# TPS2511.net
KiCad netlist of a schematic drawn in EAGLE
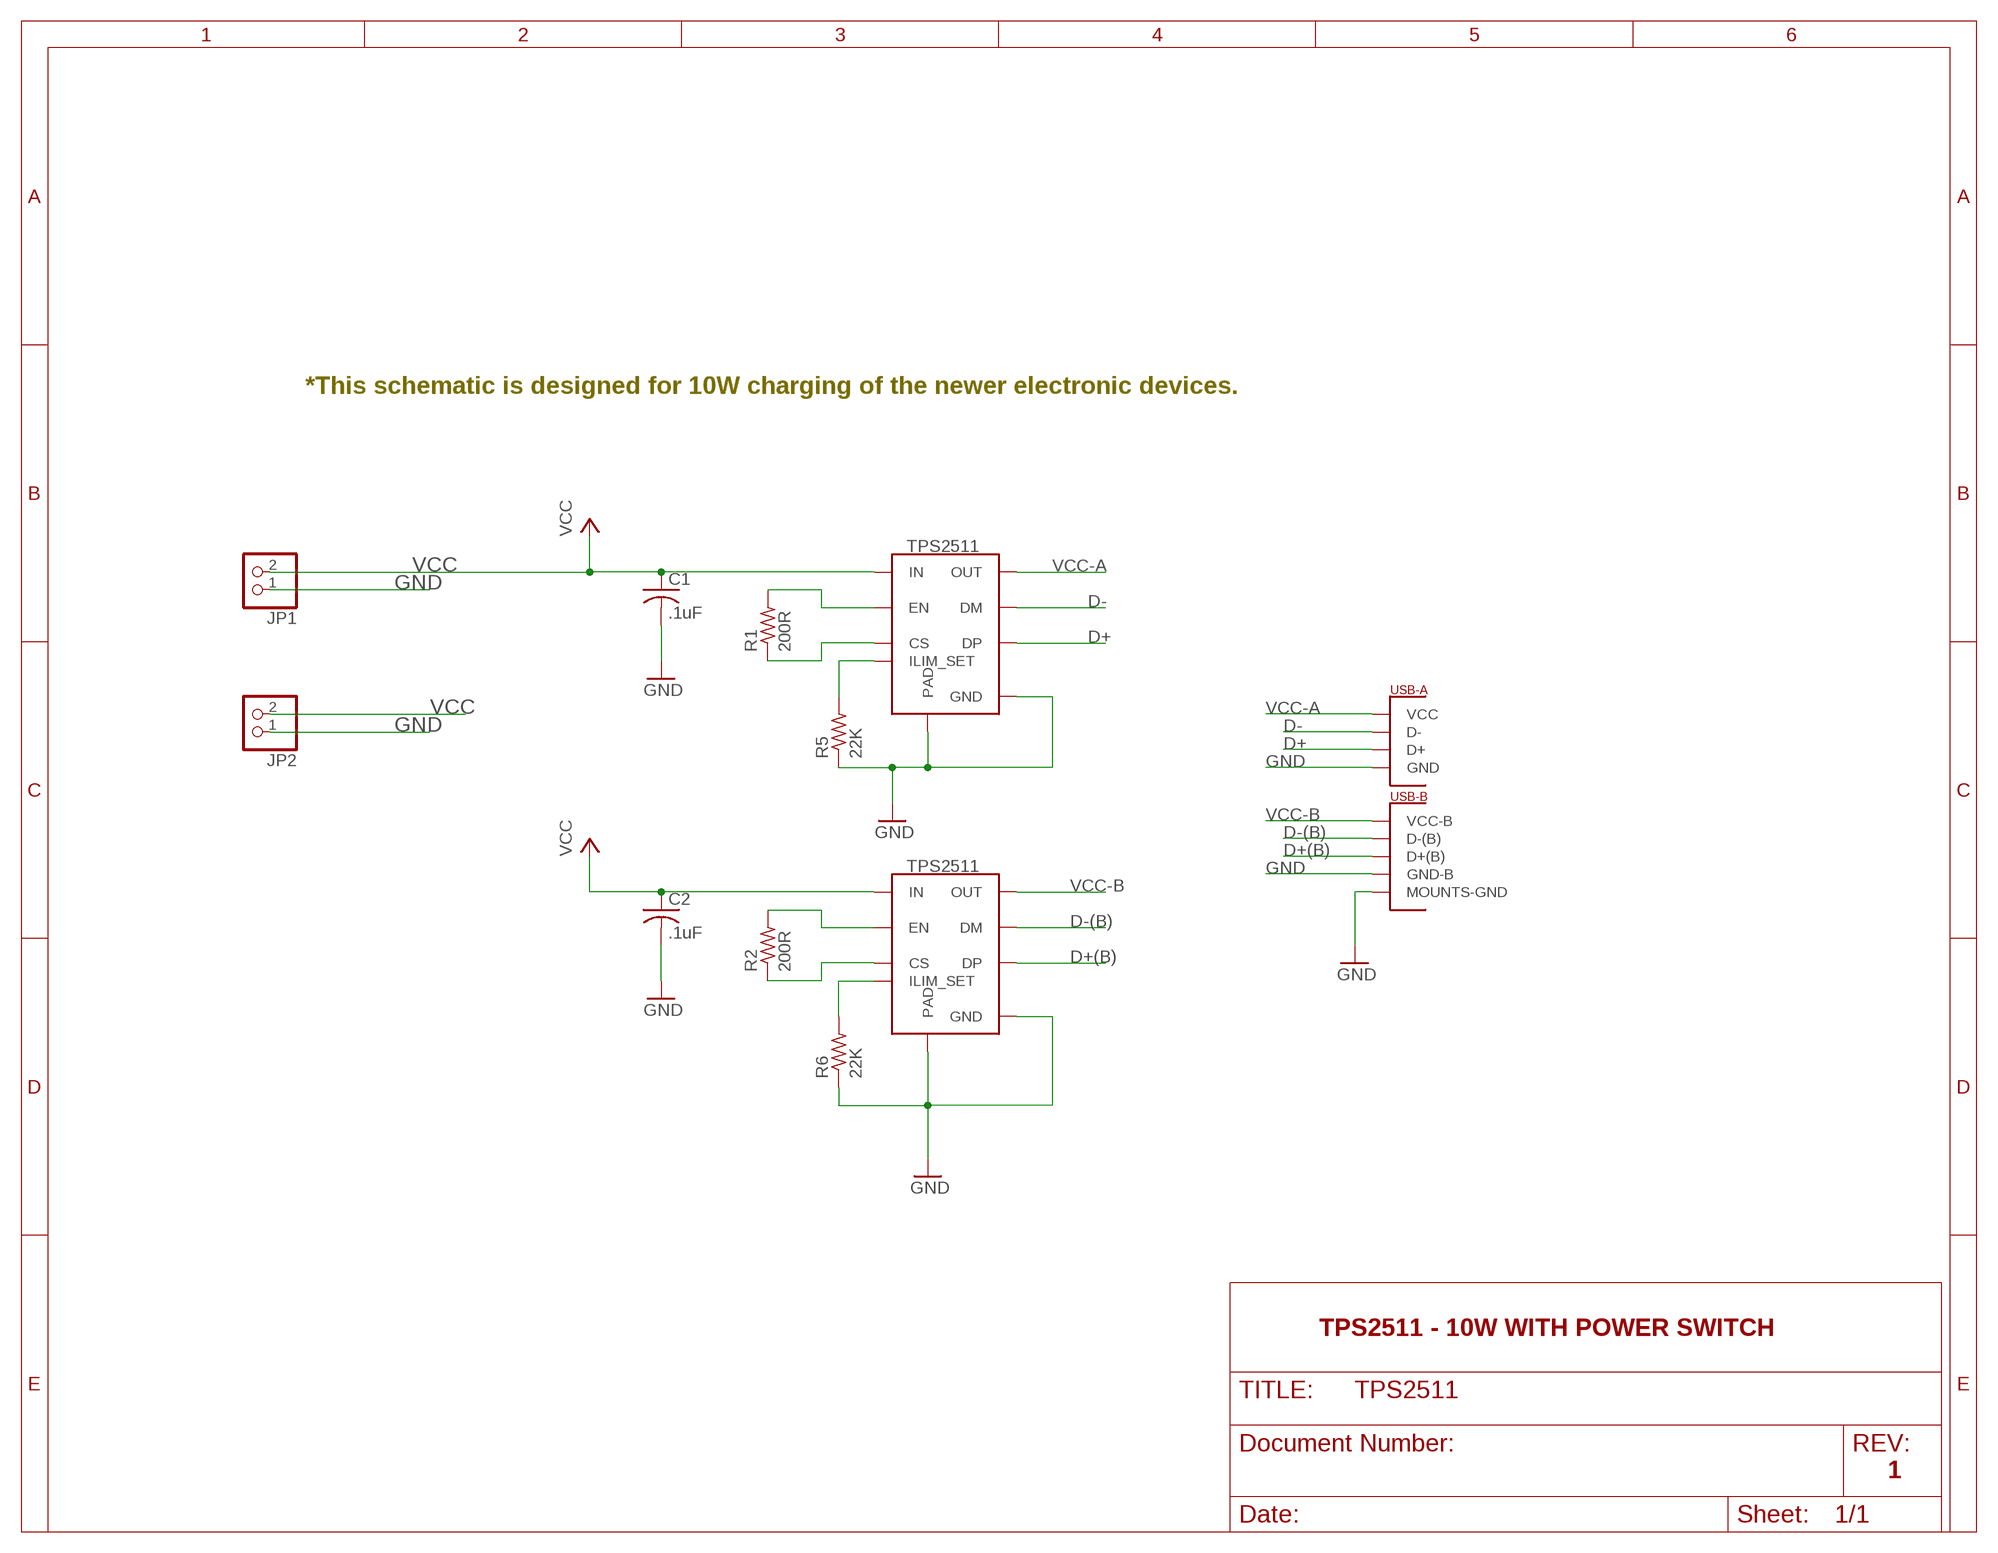
[diagram p0: schematic, sheet 1]

(export (version "E")
  (design (tool "Eeschema 10.0.6"))
  (components
    (comp (ref "C1")
      (value ".1uF")
      (footprint "eagle-import:C050-024X044")
      (libsource (lib "eagle-import") (part "C-US050-024X044"))
    )
    (comp (ref "C2")
      (value ".1uF")
      (footprint "eagle-import:C050-024X044")
      (libsource (lib "eagle-import") (part "C-US050-024X044"))
    )
    (comp (ref "JP1")
      (value "PINHD-1X2/90")
      (footprint "eagle-import:1X02_90")
      (libsource (lib "eagle-import") (part "PINHD-1X2/90"))
    )
    (comp (ref "JP2")
      (value "PINHD-1X2/90")
      (footprint "eagle-import:1X02_90")
      (libsource (lib "eagle-import") (part "PINHD-1X2/90"))
    )
    (comp (ref "R1")
      (value "200R")
      (footprint "eagle-import:0204_7")
      (libsource (lib "eagle-import") (part "R-US_0204/7"))
    )
    (comp (ref "R2")
      (value "200R")
      (footprint "eagle-import:0204_7")
      (libsource (lib "eagle-import") (part "R-US_0204/7"))
    )
    (comp (ref "R5")
      (value "22K")
      (footprint "eagle-import:0204_7")
      (libsource (lib "eagle-import") (part "R-US_0204/7"))
    )
    (comp (ref "R6")
      (value "22K")
      (footprint "eagle-import:0204_7")
      (libsource (lib "eagle-import") (part "R-US_0204/7"))
    )
    (comp (ref "U$1")
      (value "TPS2511-MSOP8")
      (footprint "eagle-import:MSOP-8")
      (libsource (lib "eagle-import") (part "TPS2511-MSOP8"))
    )
    (comp (ref "U$2")
      (value "DUAL-PORT-USB-REC")
      (footprint "eagle-import:DUAL-PORT-USB")
      (libsource (lib "eagle-import") (part "DUAL-PORT-USB-REC"))
    )
    (comp (ref "U$3")
      (value "TPS2511-MSOP8")
      (footprint "eagle-import:MSOP-8")
      (libsource (lib "eagle-import") (part "TPS2511-MSOP8"))
    )
  )
  (nets
    (net (code "1") (name "/D+") (class "Default")
      (node (ref "U$1") (pin "P$6") (pinfunction "DP_P$6") (pintype "bidirectional"))
      (node (ref "U$2") (pin "P$8") (pinfunction "D+_P$8") (pintype "bidirectional"))
    )
    (net (code "2") (name "/D+(B)") (class "Default")
      (node (ref "U$2") (pin "P$6") (pinfunction "D+(B)_P$6") (pintype "bidirectional"))
      (node (ref "U$3") (pin "P$6") (pinfunction "DP_P$6") (pintype "bidirectional"))
    )
    (net (code "3") (name "/D-") (class "Default")
      (node (ref "U$1") (pin "P$7") (pinfunction "DM_P$7") (pintype "bidirectional"))
      (node (ref "U$2") (pin "P$7") (pinfunction "D-_P$7") (pintype "bidirectional"))
    )
    (net (code "4") (name "/D-(B)") (class "Default")
      (node (ref "U$2") (pin "P$5") (pinfunction "D-(B)_P$5") (pintype "bidirectional"))
      (node (ref "U$3") (pin "P$7") (pinfunction "DM_P$7") (pintype "bidirectional"))
    )
    (net (code "5") (name "/VCC-A") (class "Default")
      (node (ref "U$1") (pin "P$8") (pinfunction "OUT_P$8") (pintype "power_in"))
      (node (ref "U$2") (pin "P$12") (pinfunction "VCC_P$12") (pintype "power_in"))
    )
    (net (code "6") (name "/VCC-B") (class "Default")
      (node (ref "U$2") (pin "P$10") (pinfunction "VCC-B_P$10") (pintype "power_in"))
      (node (ref "U$3") (pin "P$8") (pinfunction "OUT_P$8") (pintype "power_in"))
    )
    (net (code "7") (name "GND") (class "Default")
      (node (ref "C1") (pin "2") (pinfunction "2_2") (pintype "passive"))
      (node (ref "C2") (pin "2") (pinfunction "2_2") (pintype "passive"))
      (node (ref "JP1") (pin "1") (pinfunction "1_1") (pintype "passive"))
      (node (ref "JP2") (pin "1") (pinfunction "1_1") (pintype "passive"))
      (node (ref "R5") (pin "1") (pinfunction "1_1") (pintype "passive"))
      (node (ref "R6") (pin "1") (pinfunction "1_1") (pintype "passive"))
      (node (ref "U$1") (pin "P$1") (pinfunction "GND_P$1") (pintype "power_in"))
      (node (ref "U$1") (pin "P$9") (pinfunction "PAD_P$9") (pintype "power_in"))
      (node (ref "U$2") (pin "GND") (pinfunction "MOUNTS-GND_GND") (pintype "power_in"))
      (node (ref "U$2") (pin "P$11") (pinfunction "GND_P$11") (pintype "power_in"))
      (node (ref "U$2") (pin "P$2") (pinfunction "MOUNTS-GND_P$2") (pintype "power_in"))
      (node (ref "U$2") (pin "P$3") (pinfunction "MOUNTS-GND_P$3") (pintype "power_in"))
      (node (ref "U$2") (pin "P$4") (pinfunction "MOUNTS-GND_P$4") (pintype "power_in"))
      (node (ref "U$2") (pin "P$9") (pinfunction "GND-B_P$9") (pintype "power_in"))
      (node (ref "U$3") (pin "P$1") (pinfunction "GND_P$1") (pintype "power_in"))
      (node (ref "U$3") (pin "P$9") (pinfunction "PAD_P$9") (pintype "power_in"))
    )
    (net (code "8") (name "Net-(U$1-CS)") (class "Default")
      (node (ref "R1") (pin "1") (pinfunction "1_1") (pintype "passive"))
      (node (ref "U$1") (pin "P$4") (pinfunction "CS_P$4") (pintype "bidirectional"))
    )
    (net (code "9") (name "Net-(U$1-EN)") (class "Default")
      (node (ref "R1") (pin "2") (pinfunction "2_2") (pintype "passive"))
      (node (ref "U$1") (pin "P$5") (pinfunction "EN_P$5") (pintype "bidirectional"))
    )
    (net (code "10") (name "Net-(U$1-ILIM_SET)") (class "Default")
      (node (ref "R5") (pin "2") (pinfunction "2_2") (pintype "passive"))
      (node (ref "U$1") (pin "P$2") (pinfunction "ILIM_SET_P$2") (pintype "bidirectional"))
    )
    (net (code "11") (name "Net-(U$3-CS)") (class "Default")
      (node (ref "R2") (pin "1") (pinfunction "1_1") (pintype "passive"))
      (node (ref "U$3") (pin "P$4") (pinfunction "CS_P$4") (pintype "bidirectional"))
    )
    (net (code "12") (name "Net-(U$3-EN)") (class "Default")
      (node (ref "R2") (pin "2") (pinfunction "2_2") (pintype "passive"))
      (node (ref "U$3") (pin "P$5") (pinfunction "EN_P$5") (pintype "bidirectional"))
    )
    (net (code "13") (name "Net-(U$3-ILIM_SET)") (class "Default")
      (node (ref "R6") (pin "2") (pinfunction "2_2") (pintype "passive"))
      (node (ref "U$3") (pin "P$2") (pinfunction "ILIM_SET_P$2") (pintype "bidirectional"))
    )
    (net (code "14") (name "VCC") (class "Default")
      (node (ref "C1") (pin "1") (pinfunction "1_1") (pintype "passive"))
      (node (ref "C2") (pin "1") (pinfunction "1_1") (pintype "passive"))
      (node (ref "JP1") (pin "2") (pinfunction "2_2") (pintype "passive"))
      (node (ref "JP2") (pin "2") (pinfunction "2_2") (pintype "passive"))
      (node (ref "U$1") (pin "P$3") (pinfunction "IN_P$3") (pintype "power_in"))
      (node (ref "U$3") (pin "P$3") (pinfunction "IN_P$3") (pintype "power_in"))
    )
  )
)
